# main_board_power.net
KiCad netlist of a schematic drawn in Altium Designer
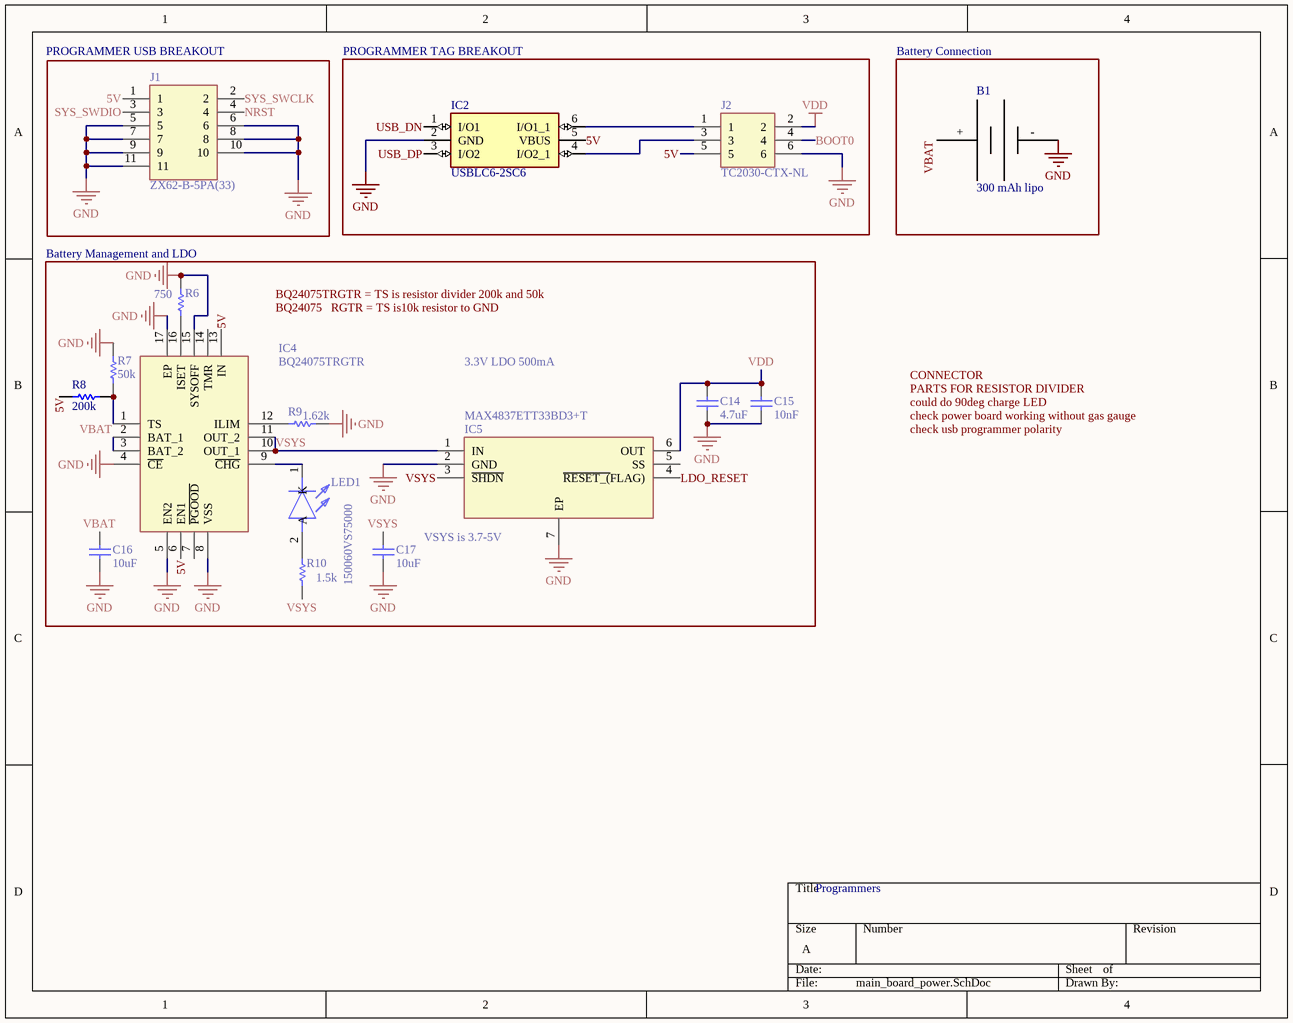
[diagram p0: main_board_power.SchDoc]

(export (version "E")
  (design (tool "Eeschema 10.0.6"))
  (components
    (comp (ref "B1")
      (value "300 mAh lipo")
      (footprint "RJD3048ST1")
      (description "Illinois Capacitor 300mAh Lipo Battery")
      (libsource (lib "david_custom") (part "RJD3048ST1"))
    )
    (comp (ref "C14")
      (value "4.7uF")
      (footprint "0402C")
      (description "Capacitor")
      (fields (field (name "Comment") "Cap") (field (name "PUBLISHER") "Altium Limited"))
      (libsource (lib "Miscellaneous Devices") (part "Cap"))
    )
    (comp (ref "C15")
      (value "10nF")
      (footprint "0402C")
      (description "Capacitor")
      (fields (field (name "Comment") "Cap") (field (name "PUBLISHER") "Altium Limited"))
      (libsource (lib "Miscellaneous Devices") (part "Cap"))
    )
    (comp (ref "C16")
      (value "10uF")
      (footprint "0402C")
      (description "Capacitor")
      (fields (field (name "Comment") "Cap") (field (name "PUBLISHER") "Altium Limited"))
      (libsource (lib "Miscellaneous Devices") (part "Cap"))
    )
    (comp (ref "C17")
      (value "10uF")
      (footprint "0402C")
      (description "Capacitor")
      (fields (field (name "Comment") "Cap") (field (name "PUBLISHER") "Altium Limited"))
      (libsource (lib "Miscellaneous Devices") (part "Cap"))
    )
    (comp (ref "IC2")
      (value "USBLC6-2SC6")
      (footprint "SOT95P280X145-6N")
      (description "Integrated Circuit")
      (fields (field (name "MOUSER PART NUMBER") "511-USBLC6-2SC6") (field (name "RS PART NUMBER") "9206266"))
      (libsource (lib "SamacSys") (part "USBLC6-2SC6"))
    )
    (comp (ref "IC4")
      (value "BQ24075TRGTR")
      (footprint "SamacSys:QFN50P300X300X100-17N-D")
      (description "Integrated Circuit")
      (fields (field (name "MOUSER PART NUMBER") "595-BQ24075TRGTR"))
      (libsource (lib "*") (part "BQ24075TRGTR"))
    )
    (comp (ref "IC5")
      (value "MAX4837ETT33BD3+T")
      (footprint "SamacSys:SON95P300X300X80-7N")
      (description "Integrated Circuit")
      (libsource (lib "SamacSys") (part "MAX4837ETT33BD3+T"))
    )
    (comp (ref "J1")
      (value "ZX62-B-5PA(33)")
      (footprint "ZX62B5PA33")
      (description "Connector")
      (fields
        (field (name "MOUSER PART NUMBER") "798-ZX62-B-5PA33")
        (field (name "RS PART NUMBER") "1362267")
      )
      (libsource (lib "SamacSys") (part "ZX62-B-5PA(33)"))
    )
    (comp (ref "J2")
      (value "TC2030-CTX-NL")
      (footprint "TC2030MCPNL10")
      (description "Connector")
      (libsource (lib "SamacSys") (part "TC2030-CTX-NL"))
    )
    (comp (ref "LED1")
      (value "150060VS75000")
      (footprint "SamacSys:LEDC1608X80N")
      (description "LED")
      (fields
        (field (name "MOUSER PART NUMBER") "710-150060VS75000")
        (field (name "RS PART NUMBER") "8154215P")
      )
      (libsource (lib "*") (part "150060VS75000"))
    )
    (comp (ref "R6")
      (value "750")
      (footprint "0402R")
      (libsource (lib "glasses_full_v1_small") (part "Resistor"))
    )
    (comp (ref "R7")
      (value "50k")
      (footprint "0402R")
      (libsource (lib "glasses_full_v1_small") (part "Resistor"))
    )
    (comp (ref "R8")
      (value "200k")
      (footprint "0402R")
      (libsource (lib "glasses_full_v1_small") (part "Resistor"))
    )
    (comp (ref "R9")
      (value "1.62k")
      (footprint "0402R")
      (libsource (lib "glasses_full_v1_small") (part "Resistor"))
    )
    (comp (ref "R10")
      (value "1.5k")
      (footprint "0402R")
      (libsource (lib "glasses_full_v1_small") (part "Resistor"))
    )
  )
  (nets
    (net (code "1") (name "/5V") (class "Default")
      (node (ref "IC2") (pin "5") (pinfunction "VBUS_5") (pintype "passive"))
      (node (ref "IC4") (pin "13") (pinfunction "IN_13") (pintype "passive"))
      (node (ref "IC4") (pin "6") (pinfunction "EN1_6") (pintype "passive"))
      (node (ref "J1") (pin "1") (pinfunction "1_1") (pintype "passive"))
      (node (ref "J2") (pin "5") (pinfunction "5_5") (pintype "passive"))
      (node (ref "R8") (pin "1") (pinfunction "1_1") (pintype "passive"))
    )
    (net (code "2") (name "/BOOT0") (class "Default")
      (node (ref "J2") (pin "4") (pinfunction "4_4") (pintype "passive"))
    )
    (net (code "6") (name "/LDO_RESET") (class "Default")
      (node (ref "IC5") (pin "4") (pinfunction "~{RESET_(}FLAG)_4") (pintype "passive"))
    )
    (net (code "7") (name "/NRST") (class "Default")
      (node (ref "J1") (pin "4") (pinfunction "4_4") (pintype "passive"))
    )
    (net (code "9") (name "/SYS_SWCLK") (class "Default")
      (node (ref "J1") (pin "2") (pinfunction "2_2") (pintype "passive"))
    )
    (net (code "10") (name "/SYS_SWDIO") (class "Default")
      (node (ref "J1") (pin "3") (pinfunction "3_3") (pintype "passive"))
    )
    (net (code "11") (name "/USB_DN") (class "Default")
      (node (ref "IC2") (pin "1") (pinfunction "I/O1_1") (pintype "bidirectional"))
    )
    (net (code "12") (name "/USB_DP") (class "Default")
      (node (ref "IC2") (pin "3") (pinfunction "I/O2_3") (pintype "bidirectional"))
    )
    (net (code "13") (name "/VBAT") (class "Default")
      (node (ref "B1") (pin "+") (pinfunction "2_+") (pintype "passive"))
      (node (ref "C16") (pin "1") (pinfunction "1_1") (pintype "passive"))
      (node (ref "IC4") (pin "2") (pinfunction "BAT_1_2") (pintype "passive"))
      (node (ref "IC4") (pin "3") (pinfunction "BAT_2_3") (pintype "passive"))
    )
    (net (code "14") (name "/VSYS") (class "Default")
      (node (ref "C17") (pin "1") (pinfunction "1_1") (pintype "passive"))
      (node (ref "IC4") (pin "10") (pinfunction "OUT_1_10") (pintype "passive"))
      (node (ref "IC4") (pin "11") (pinfunction "OUT_2_11") (pintype "passive"))
      (node (ref "IC5") (pin "1") (pinfunction "IN_1") (pintype "passive"))
      (node (ref "IC5") (pin "3") (pinfunction "~{SHDN}_3") (pintype "passive"))
      (node (ref "R10") (pin "2") (pinfunction "2_2") (pintype "passive"))
    )
    (net (code "18") (name "GND") (class "Default")
      (node (ref "B1") (pin "-") (pinfunction "1_-") (pintype "passive"))
      (node (ref "C14") (pin "2") (pinfunction "2_2") (pintype "passive"))
      (node (ref "C15") (pin "2") (pinfunction "2_2") (pintype "passive"))
      (node (ref "C16") (pin "2") (pinfunction "2_2") (pintype "passive"))
      (node (ref "C17") (pin "2") (pinfunction "2_2") (pintype "passive"))
      (node (ref "IC2") (pin "2") (pinfunction "GND_2") (pintype "power_in"))
      (node (ref "IC4") (pin "15") (pinfunction "SYSOFF_15") (pintype "passive"))
      (node (ref "IC4") (pin "17") (pinfunction "EP_17") (pintype "passive"))
      (node (ref "IC4") (pin "4") (pinfunction "~{CE}_4") (pintype "passive"))
      (node (ref "IC4") (pin "5") (pinfunction "EN2_5") (pintype "passive"))
      (node (ref "IC4") (pin "8") (pinfunction "VSS_8") (pintype "passive"))
      (node (ref "IC5") (pin "2") (pinfunction "GND_2") (pintype "passive"))
      (node (ref "IC5") (pin "7") (pinfunction "EP_7") (pintype "passive"))
      (node (ref "J1") (pin "10") (pinfunction "10_10") (pintype "passive"))
      (node (ref "J1") (pin "11") (pinfunction "11_11") (pintype "passive"))
      (node (ref "J1") (pin "5") (pinfunction "5_5") (pintype "passive"))
      (node (ref "J1") (pin "6") (pinfunction "6_6") (pintype "passive"))
      (node (ref "J1") (pin "7") (pinfunction "7_7") (pintype "passive"))
      (node (ref "J1") (pin "8") (pinfunction "8_8") (pintype "passive"))
      (node (ref "J1") (pin "9") (pinfunction "9_9") (pintype "passive"))
      (node (ref "J2") (pin "6") (pinfunction "6_6") (pintype "passive"))
      (node (ref "R6") (pin "1") (pinfunction "1_1") (pintype "passive"))
      (node (ref "R7") (pin "1") (pinfunction "1_1") (pintype "passive"))
      (node (ref "R9") (pin "2") (pinfunction "2_2") (pintype "passive"))
    )
    (net (code "19") (name "Net-(IC2-I{slash}O1_1)") (class "Default")
      (node (ref "IC2") (pin "6") (pinfunction "I/O1_1_6") (pintype "bidirectional"))
      (node (ref "J2") (pin "1") (pinfunction "1_1") (pintype "passive"))
    )
    (net (code "20") (name "Net-(IC2-I{slash}O2_1)") (class "Default")
      (node (ref "IC2") (pin "4") (pinfunction "I/O2_1_4") (pintype "bidirectional"))
      (node (ref "J2") (pin "3") (pinfunction "3_3") (pintype "passive"))
    )
    (net (code "21") (name "Net-(IC4-ILIM)") (class "Default")
      (node (ref "IC4") (pin "12") (pinfunction "ILIM_12") (pintype "passive"))
      (node (ref "R9") (pin "1") (pinfunction "1_1") (pintype "passive"))
    )
    (net (code "22") (name "Net-(IC4-ISET)") (class "Default")
      (node (ref "IC4") (pin "16") (pinfunction "ISET_16") (pintype "passive"))
      (node (ref "R6") (pin "2") (pinfunction "2_2") (pintype "passive"))
    )
    (net (code "23") (name "Net-(IC4-TS)") (class "Default")
      (node (ref "IC4") (pin "1") (pinfunction "TS_1") (pintype "passive"))
      (node (ref "R7") (pin "2") (pinfunction "2_2") (pintype "passive"))
      (node (ref "R8") (pin "2") (pinfunction "2_2") (pintype "passive"))
    )
    (net (code "24") (name "Net-(IC4-~{CHG})") (class "Default")
      (node (ref "IC4") (pin "9") (pinfunction "~{CHG}_9") (pintype "passive"))
      (node (ref "LED1") (pin "1") (pinfunction "K_1") (pintype "passive"))
    )
    (net (code "25") (name "Net-(LED1-A)") (class "Default")
      (node (ref "LED1") (pin "2") (pinfunction "A_2") (pintype "passive"))
      (node (ref "R10") (pin "1") (pinfunction "1_1") (pintype "passive"))
    )
    (net (code "26") (name "VDD") (class "Default")
      (node (ref "C14") (pin "1") (pinfunction "1_1") (pintype "passive"))
      (node (ref "C15") (pin "1") (pinfunction "1_1") (pintype "passive"))
      (node (ref "IC5") (pin "6") (pinfunction "OUT_6") (pintype "passive"))
      (node (ref "J2") (pin "2") (pinfunction "2_2") (pintype "passive"))
    )
    (net (code "27") (name "unconnected-(IC4-TMR-Pad14)") (class "Default")
      (node (ref "IC4") (pin "14") (pinfunction "TMR_14") (pintype "passive"))
    )
    (net (code "28") (name "unconnected-(IC4-~{PGOOD}-Pad7)") (class "Default")
      (node (ref "IC4") (pin "7") (pinfunction "~{PGOOD}_7") (pintype "passive"))
    )
    (net (code "29") (name "unconnected-(IC5-SS-Pad5)") (class "Default")
      (node (ref "IC5") (pin "5") (pinfunction "SS_5") (pintype "passive"))
    )
  )
)
